# Firefly.net
KiCad netlist of a schematic drawn in EAGLE
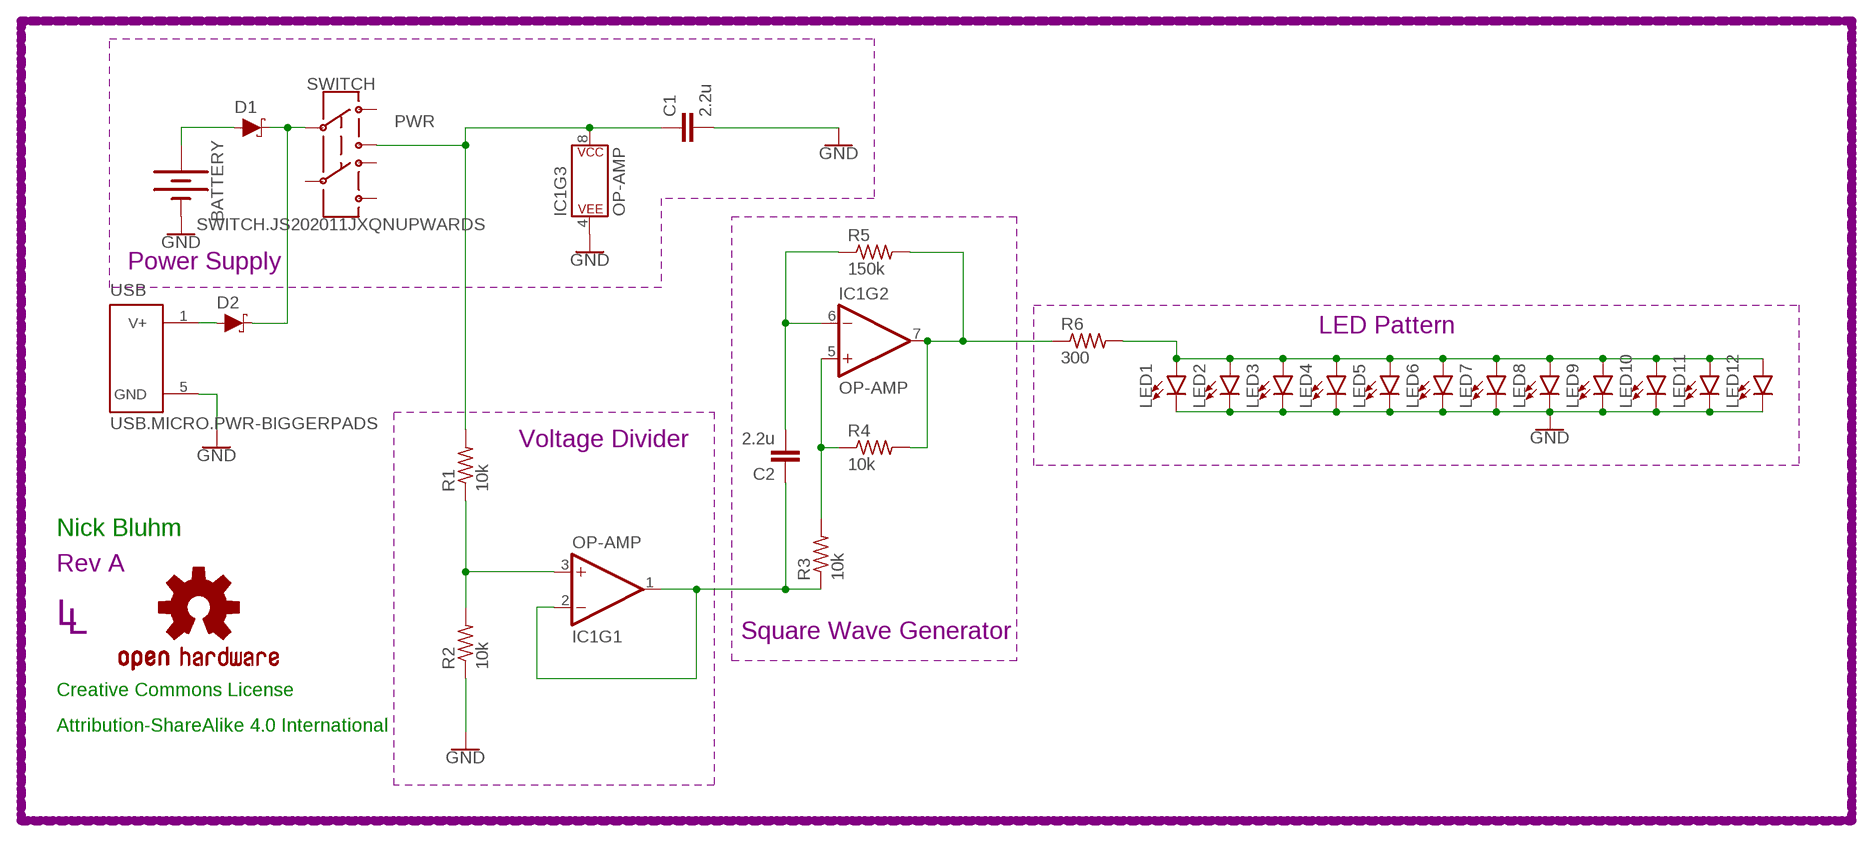
[diagram p0: schematic, sheet 1]

(export (version "E")
  (design (tool "Eeschema 10.0.6"))
  (components
    (comp (ref "BATTERY")
      (value "BATTERY-20MM_SMD")
      (footprint "eagle-import:BATTCON_20MM")
      (libsource (lib "eagle-import") (part "BATTERY-20MM_SMD"))
    )
    (comp (ref "C1")
      (value "2.2u")
      (footprint "eagle-import:C0603")
      (libsource (lib "eagle-import") (part "CAPACITOR0603"))
    )
    (comp (ref "C2")
      (value "2.2u")
      (footprint "eagle-import:C0603")
      (libsource (lib "eagle-import") (part "CAPACITOR0603"))
    )
    (comp (ref "D1")
      (value "SCHOTTKY-USC")
      (footprint "eagle-import:USC")
      (libsource (lib "eagle-import") (part "SCHOTTKY-USC"))
    )
    (comp (ref "D2")
      (value "SCHOTTKY-USC")
      (footprint "eagle-import:USC")
      (libsource (lib "eagle-import") (part "SCHOTTKY-USC"))
    )
    (comp (ref "IC1")
      (value "OP-AMP")
      (footprint "eagle-import:SO08")
      (libsource (lib "eagle-import") (part "OPAMP-DUALU"))
    )
    (comp (ref "LED1")
      (value "LED5MM")
      (footprint "eagle-import:LED_5MM")
      (libsource (lib "eagle-import") (part "LED5MM"))
    )
    (comp (ref "LED2")
      (value "LED5MM")
      (footprint "eagle-import:LED_5MM")
      (libsource (lib "eagle-import") (part "LED5MM"))
    )
    (comp (ref "LED3")
      (value "LED5MM")
      (footprint "eagle-import:LED_5MM")
      (libsource (lib "eagle-import") (part "LED5MM"))
    )
    (comp (ref "LED4")
      (value "LED5MM")
      (footprint "eagle-import:LED_5MM")
      (libsource (lib "eagle-import") (part "LED5MM"))
    )
    (comp (ref "LED5")
      (value "LED5MM")
      (footprint "eagle-import:LED_5MM")
      (libsource (lib "eagle-import") (part "LED5MM"))
    )
    (comp (ref "LED6")
      (value "LED5MM")
      (footprint "eagle-import:LED_5MM")
      (libsource (lib "eagle-import") (part "LED5MM"))
    )
    (comp (ref "LED7")
      (value "LED5MM")
      (footprint "eagle-import:LED_5MM")
      (libsource (lib "eagle-import") (part "LED5MM"))
    )
    (comp (ref "LED8")
      (value "LED5MM")
      (footprint "eagle-import:LED_5MM")
      (libsource (lib "eagle-import") (part "LED5MM"))
    )
    (comp (ref "LED9")
      (value "LED5MM")
      (footprint "eagle-import:LED_5MM")
      (libsource (lib "eagle-import") (part "LED5MM"))
    )
    (comp (ref "LED10")
      (value "LED5MM")
      (footprint "eagle-import:LED_5MM")
      (libsource (lib "eagle-import") (part "LED5MM"))
    )
    (comp (ref "LED11")
      (value "LED5MM")
      (footprint "eagle-import:LED_5MM")
      (libsource (lib "eagle-import") (part "LED5MM"))
    )
    (comp (ref "LED12")
      (value "LED5MM")
      (footprint "eagle-import:LED_5MM")
      (libsource (lib "eagle-import") (part "LED5MM"))
    )
    (comp (ref "LOGO1")
      (value "OSHW-LOGOL")
      (footprint "eagle-import:OSHW-LOGO-L")
      (libsource (lib "eagle-import") (part "OSHW-LOGOL"))
    )
    (comp (ref "R1")
      (value "10k")
      (footprint "eagle-import:R0603")
      (libsource (lib "eagle-import") (part "RESISTOR0603"))
    )
    (comp (ref "R2")
      (value "10k")
      (footprint "eagle-import:R0603")
      (libsource (lib "eagle-import") (part "RESISTOR0603"))
    )
    (comp (ref "R3")
      (value "10k")
      (footprint "eagle-import:R0603")
      (libsource (lib "eagle-import") (part "RESISTOR0603"))
    )
    (comp (ref "R4")
      (value "10k")
      (footprint "eagle-import:R0603")
      (libsource (lib "eagle-import") (part "RESISTOR0603"))
    )
    (comp (ref "R5")
      (value "150k")
      (footprint "eagle-import:R0603")
      (libsource (lib "eagle-import") (part "RESISTOR0603"))
    )
    (comp (ref "R6")
      (value "300")
      (footprint "eagle-import:R0603")
      (libsource (lib "eagle-import") (part "RESISTOR0603"))
    )
    (comp (ref "SWITCH")
      (value "SWITCH.JS202011JXQNUPWARDS")
      (footprint "eagle-import:SWITCH.00")
      (libsource (lib "eagle-import") (part "SWITCH.JS202011JXQNUPWARDS"))
    )
    (comp (ref "U$4")
      (value "REVISION.A")
      (footprint "eagle-import:REV.A")
      (libsource (lib "eagle-import") (part "REVISION.A"))
    )
    (comp (ref "U$5")
      (value "LINNES.LAB.LOGO")
      (footprint "eagle-import:LINNES.LAB.LOGO")
      (libsource (lib "eagle-import") (part "LINNES.LAB.LOGO"))
    )
    (comp (ref "USB")
      (value "USB.MICRO.PWR-BIGGERPADS")
      (footprint "eagle-import:USB-MICRO-01.BIGGERPADS.PWR")
      (libsource (lib "eagle-import") (part "USB.MICRO.PWR-BIGGERPADS"))
    )
  )
  (nets
    (net (code "1") (name "/PWR") (class "Default")
      (node (ref "C1") (pin "1") (pinfunction "1_1") (pintype "passive"))
      (node (ref "IC1") (pin "8") (pinfunction "P$V+_8") (pintype "bidirectional"))
      (node (ref "R1") (pin "2") (pinfunction "2_2") (pintype "passive"))
      (node (ref "SWITCH") (pin "3") (pinfunction "3_3") (pintype "bidirectional"))
    )
    (net (code "2") (name "GND") (class "Default")
      (node (ref "BATTERY") (pin "2") (pinfunction "-_2") (pintype "power_in"))
      (node (ref "C1") (pin "2") (pinfunction "2_2") (pintype "passive"))
      (node (ref "IC1") (pin "4") (pinfunction "P$V-_4") (pintype "bidirectional"))
      (node (ref "LED1") (pin "K") (pinfunction "C_K") (pintype "passive"))
      (node (ref "LED10") (pin "K") (pinfunction "C_K") (pintype "passive"))
      (node (ref "LED11") (pin "K") (pinfunction "C_K") (pintype "passive"))
      (node (ref "LED12") (pin "K") (pinfunction "C_K") (pintype "passive"))
      (node (ref "LED2") (pin "K") (pinfunction "C_K") (pintype "passive"))
      (node (ref "LED3") (pin "K") (pinfunction "C_K") (pintype "passive"))
      (node (ref "LED4") (pin "K") (pinfunction "C_K") (pintype "passive"))
      (node (ref "LED5") (pin "K") (pinfunction "C_K") (pintype "passive"))
      (node (ref "LED6") (pin "K") (pinfunction "C_K") (pintype "passive"))
      (node (ref "LED7") (pin "K") (pinfunction "C_K") (pintype "passive"))
      (node (ref "LED8") (pin "K") (pinfunction "C_K") (pintype "passive"))
      (node (ref "LED9") (pin "K") (pinfunction "C_K") (pintype "passive"))
      (node (ref "R2") (pin "1") (pinfunction "1_1") (pintype "passive"))
      (node (ref "USB") (pin "5") (pinfunction "GND_5") (pintype "bidirectional"))
    )
    (net (code "3") (name "Net-(BATTERY-+)") (class "Default")
      (node (ref "BATTERY") (pin "1") (pinfunction "+_1") (pintype "power_in"))
      (node (ref "D1") (pin "+") (pinfunction "A_+") (pintype "passive"))
    )
    (net (code "4") (name "Net-(D1-C)") (class "Default")
      (node (ref "D1") (pin "-") (pinfunction "C_-") (pintype "passive"))
      (node (ref "D2") (pin "-") (pinfunction "C_-") (pintype "passive"))
      (node (ref "SWITCH") (pin "2") (pinfunction "2_2") (pintype "bidirectional"))
    )
    (net (code "5") (name "Net-(D2-A)") (class "Default")
      (node (ref "D2") (pin "+") (pinfunction "A_+") (pintype "passive"))
      (node (ref "USB") (pin "1") (pinfunction "V+_1") (pintype "bidirectional"))
    )
    (net (code "6") (name "Net-(IC1A-+IN)") (class "Default")
      (node (ref "IC1") (pin "3") (pinfunction "+IN_3") (pintype "input"))
      (node (ref "R1") (pin "1") (pinfunction "1_1") (pintype "passive"))
      (node (ref "R2") (pin "2") (pinfunction "2_2") (pintype "passive"))
    )
    (net (code "7") (name "Net-(IC1A--IN)") (class "Default")
      (node (ref "C2") (pin "1") (pinfunction "1_1") (pintype "passive"))
      (node (ref "IC1") (pin "1") (pinfunction "OUT_1") (pintype "output"))
      (node (ref "IC1") (pin "2") (pinfunction "-IN_2") (pintype "input"))
      (node (ref "R3") (pin "1") (pinfunction "1_1") (pintype "passive"))
    )
    (net (code "8") (name "Net-(IC1B-+IN)") (class "Default")
      (node (ref "IC1") (pin "5") (pinfunction "+IN_5") (pintype "input"))
      (node (ref "R3") (pin "2") (pinfunction "2_2") (pintype "passive"))
      (node (ref "R4") (pin "1") (pinfunction "1_1") (pintype "passive"))
    )
    (net (code "9") (name "Net-(IC1B--IN)") (class "Default")
      (node (ref "C2") (pin "2") (pinfunction "2_2") (pintype "passive"))
      (node (ref "IC1") (pin "6") (pinfunction "-IN_6") (pintype "input"))
      (node (ref "R5") (pin "1") (pinfunction "1_1") (pintype "passive"))
    )
    (net (code "10") (name "Net-(IC1B-OUT)") (class "Default")
      (node (ref "IC1") (pin "7") (pinfunction "OUT_7") (pintype "output"))
      (node (ref "R4") (pin "2") (pinfunction "2_2") (pintype "passive"))
      (node (ref "R5") (pin "2") (pinfunction "2_2") (pintype "passive"))
      (node (ref "R6") (pin "1") (pinfunction "1_1") (pintype "passive"))
    )
    (net (code "11") (name "Net-(LED1-PadA)") (class "Default")
      (node (ref "LED1") (pin "A") (pinfunction "A_A") (pintype "passive"))
      (node (ref "LED10") (pin "A") (pinfunction "A_A") (pintype "passive"))
      (node (ref "LED11") (pin "A") (pinfunction "A_A") (pintype "passive"))
      (node (ref "LED12") (pin "A") (pinfunction "A_A") (pintype "passive"))
      (node (ref "LED2") (pin "A") (pinfunction "A_A") (pintype "passive"))
      (node (ref "LED3") (pin "A") (pinfunction "A_A") (pintype "passive"))
      (node (ref "LED4") (pin "A") (pinfunction "A_A") (pintype "passive"))
      (node (ref "LED5") (pin "A") (pinfunction "A_A") (pintype "passive"))
      (node (ref "LED6") (pin "A") (pinfunction "A_A") (pintype "passive"))
      (node (ref "LED7") (pin "A") (pinfunction "A_A") (pintype "passive"))
      (node (ref "LED8") (pin "A") (pinfunction "A_A") (pintype "passive"))
      (node (ref "LED9") (pin "A") (pinfunction "A_A") (pintype "passive"))
      (node (ref "R6") (pin "2") (pinfunction "2_2") (pintype "passive"))
    )
    (net (code "12") (name "unconnected-(SWITCH-Pad1)") (class "Default")
      (node (ref "SWITCH") (pin "1") (pinfunction "1_1") (pintype "bidirectional"))
    )
    (net (code "13") (name "unconnected-(SWITCH-Pad5)") (class "Default")
      (node (ref "SWITCH") (pin "5") (pinfunction "5_5") (pintype "bidirectional"))
    )
    (net (code "14") (name "unconnected-(SWITCH-Pad6)") (class "Default")
      (node (ref "SWITCH") (pin "6") (pinfunction "6_6") (pintype "bidirectional"))
    )
    (net (code "15") (name "unconnected-(SWITCH-Pad7)") (class "Default")
      (node (ref "SWITCH") (pin "7") (pinfunction "7_7") (pintype "bidirectional"))
    )
  )
)
